# Full-Wave_Rectifier.net
KiCad netlist of a schematic drawn in Altium Designer
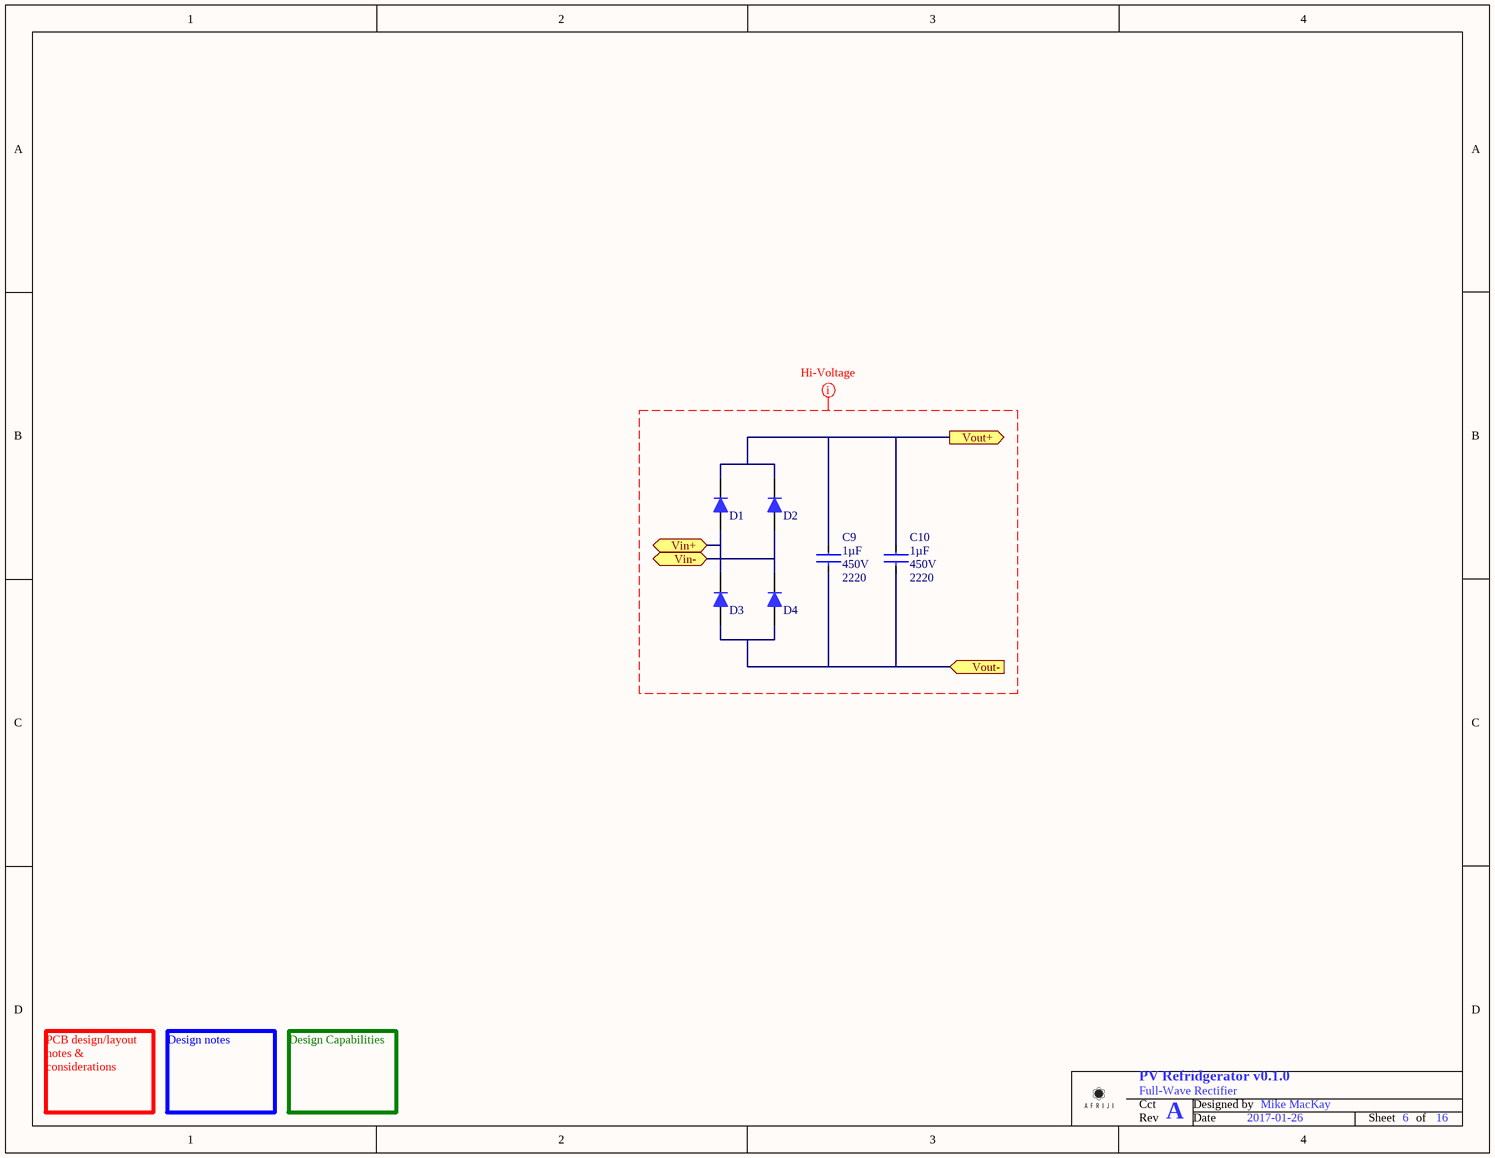
[diagram p0: Full-Wave Rectifier.schdoc]

(export (version "E")
  (design (tool "Eeschema 10.0.6"))
  (components
    (comp (ref "C9")
      (value "1uF 2220 450V")
      (footprint "C2220 - Ceramic")
      (fields
        (field (name "MANUFACTURER") "TDK Corporation")
        (field (name "MANUFACTURER PART NUMBER") "CGA9P4X7T2W105M250KE")
        (field (name "TOLERANCE") "±20%")
        (field (name "CAPACITANCE") "1µF")
        (field (name "VOLTAGE - RATED") "450V")
        (field (name "PACKAGE / CASE") "2220")
      )
      (libsource (lib "Local Library") (part "1uF 2220 450V"))
    )
    (comp (ref "C10")
      (value "1uF 2220 450V")
      (footprint "C2220 - Ceramic")
      (fields
        (field (name "MANUFACTURER") "TDK Corporation")
        (field (name "MANUFACTURER PART NUMBER") "CGA9P4X7T2W105M250KE")
        (field (name "TOLERANCE") "±20%")
        (field (name "CAPACITANCE") "1µF")
        (field (name "VOLTAGE - RATED") "450V")
        (field (name "PACKAGE / CASE") "2220")
      )
      (libsource (lib "Local Library") (part "1uF 2220 450V"))
    )
    (comp (ref "D1")
      (value "~")
      (footprint "SMA - Diode")
      (description "Signal Diode")
      (fields
        (field (name "MANUFACTURER") "Vishay Semiconductor Diodes Division")
        (field (name "MANUFACTURER PART NUMBER") "US1G-E3/5AT")
      )
      (libsource (lib "Integrated Component Library") (part "Diode - Signal 1A"))
    )
    (comp (ref "D2")
      (value "~")
      (footprint "SMA - Diode")
      (description "Signal Diode")
      (fields
        (field (name "MANUFACTURER") "Vishay Semiconductor Diodes Division")
        (field (name "MANUFACTURER PART NUMBER") "US1G-E3/5AT")
      )
      (libsource (lib "Integrated Component Library") (part "Diode - Signal 1A"))
    )
    (comp (ref "D3")
      (value "~")
      (footprint "SMA - Diode")
      (description "Signal Diode")
      (fields
        (field (name "MANUFACTURER") "Vishay Semiconductor Diodes Division")
        (field (name "MANUFACTURER PART NUMBER") "US1G-E3/5AT")
      )
      (libsource (lib "Integrated Component Library") (part "Diode - Signal 1A"))
    )
    (comp (ref "D4")
      (value "~")
      (footprint "SMA - Diode")
      (description "Signal Diode")
      (fields
        (field (name "MANUFACTURER") "Vishay Semiconductor Diodes Division")
        (field (name "MANUFACTURER PART NUMBER") "US1G-E3/5AT")
      )
      (libsource (lib "Integrated Component Library") (part "Diode - Signal 1A"))
    )
  )
  (nets
    (net (code "1") (name "/Vin+") (class "Default")
      (node (ref "D1") (pin "1") (pinfunction "Anode_1") (pintype "passive"))
      (node (ref "D3") (pin "2") (pinfunction "Cathode_2") (pintype "passive"))
    )
    (net (code "2") (name "/Vin-") (class "Default")
      (node (ref "D2") (pin "1") (pinfunction "Anode_1") (pintype "passive"))
      (node (ref "D4") (pin "2") (pinfunction "Cathode_2") (pintype "passive"))
    )
    (net (code "3") (name "/Vout+") (class "Default")
      (node (ref "C10") (pin "2") (pinfunction "2_2") (pintype "passive"))
      (node (ref "C9") (pin "2") (pinfunction "2_2") (pintype "passive"))
      (node (ref "D1") (pin "2") (pinfunction "Cathode_2") (pintype "passive"))
      (node (ref "D2") (pin "2") (pinfunction "Cathode_2") (pintype "passive"))
    )
    (net (code "4") (name "/Vout-") (class "Default")
      (node (ref "C10") (pin "1") (pinfunction "1_1") (pintype "passive"))
      (node (ref "C9") (pin "1") (pinfunction "1_1") (pintype "passive"))
      (node (ref "D3") (pin "1") (pinfunction "Anode_1") (pintype "passive"))
      (node (ref "D4") (pin "1") (pinfunction "Anode_1") (pintype "passive"))
    )
  )
)
